# PianoPCB.net
KiCad netlist of a schematic drawn in EAGLE
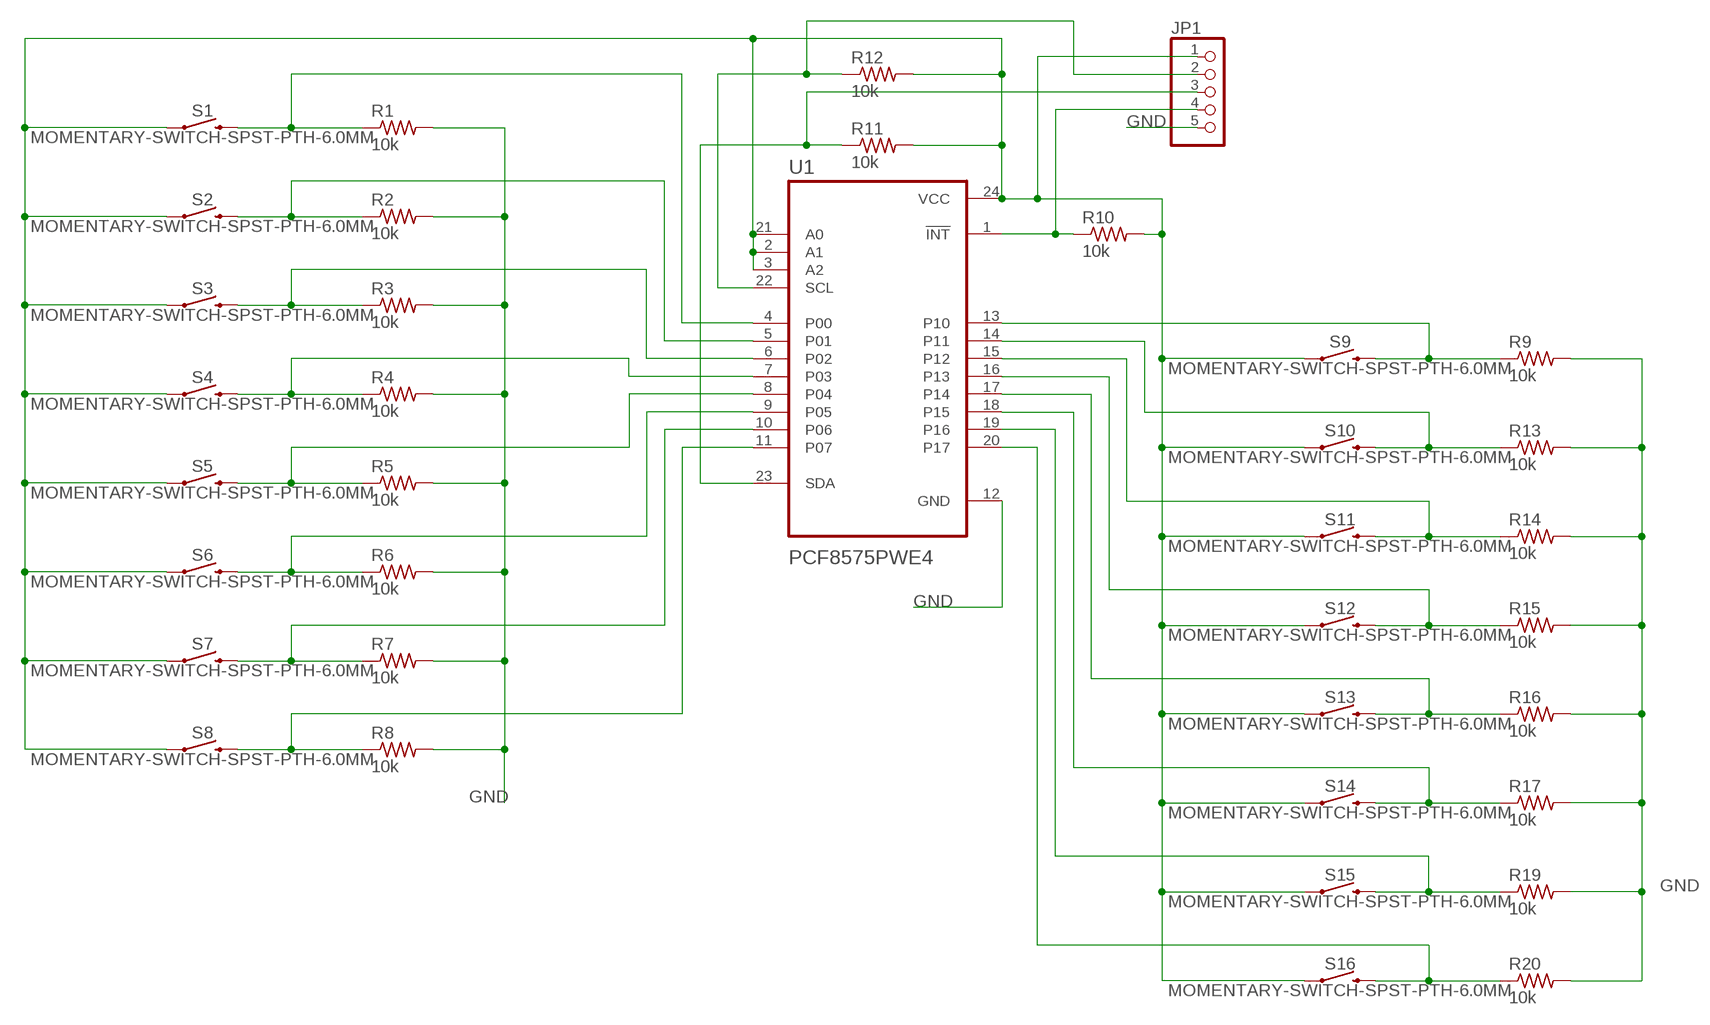
[diagram p0: schematic, sheet 1]

(export (version "E")
  (design (tool "Eeschema 10.0.6"))
  (components
    (comp (ref "JP1")
      (value "PINHD-1X5")
      (footprint "eagle-import:1X05")
      (libsource (lib "eagle-import") (part "PINHD-1X5"))
    )
    (comp (ref "R1")
      (value "10k")
      (footprint "eagle-import:0207_10")
      (libsource (lib "eagle-import") (part "R-US_0207/10"))
    )
    (comp (ref "R2")
      (value "10k")
      (footprint "eagle-import:0207_10")
      (libsource (lib "eagle-import") (part "R-US_0207/10"))
    )
    (comp (ref "R3")
      (value "10k")
      (footprint "eagle-import:0207_10")
      (libsource (lib "eagle-import") (part "R-US_0207/10"))
    )
    (comp (ref "R4")
      (value "10k")
      (footprint "eagle-import:0207_10")
      (libsource (lib "eagle-import") (part "R-US_0207/10"))
    )
    (comp (ref "R5")
      (value "10k")
      (footprint "eagle-import:0207_10")
      (libsource (lib "eagle-import") (part "R-US_0207/10"))
    )
    (comp (ref "R6")
      (value "10k")
      (footprint "eagle-import:0207_10")
      (libsource (lib "eagle-import") (part "R-US_0207/10"))
    )
    (comp (ref "R7")
      (value "10k")
      (footprint "eagle-import:0207_10")
      (libsource (lib "eagle-import") (part "R-US_0207/10"))
    )
    (comp (ref "R8")
      (value "10k")
      (footprint "eagle-import:0207_10")
      (libsource (lib "eagle-import") (part "R-US_0207/10"))
    )
    (comp (ref "R9")
      (value "10k")
      (footprint "eagle-import:0207_10")
      (libsource (lib "eagle-import") (part "R-US_0207/10"))
    )
    (comp (ref "R10")
      (value "10k")
      (footprint "eagle-import:0207_10")
      (libsource (lib "eagle-import") (part "R-US_0207/10"))
    )
    (comp (ref "R11")
      (value "10k")
      (footprint "eagle-import:0207_10")
      (libsource (lib "eagle-import") (part "R-US_0207/10"))
    )
    (comp (ref "R12")
      (value "10k")
      (footprint "eagle-import:0207_10")
      (libsource (lib "eagle-import") (part "R-US_0207/10"))
    )
    (comp (ref "R13")
      (value "10k")
      (footprint "eagle-import:0207_10")
      (libsource (lib "eagle-import") (part "R-US_0207/10"))
    )
    (comp (ref "R14")
      (value "10k")
      (footprint "eagle-import:0207_10")
      (libsource (lib "eagle-import") (part "R-US_0207/10"))
    )
    (comp (ref "R15")
      (value "10k")
      (footprint "eagle-import:0207_10")
      (libsource (lib "eagle-import") (part "R-US_0207/10"))
    )
    (comp (ref "R16")
      (value "10k")
      (footprint "eagle-import:0207_10")
      (libsource (lib "eagle-import") (part "R-US_0207/10"))
    )
    (comp (ref "R17")
      (value "10k")
      (footprint "eagle-import:0207_10")
      (libsource (lib "eagle-import") (part "R-US_0207/10"))
    )
    (comp (ref "R19")
      (value "10k")
      (footprint "eagle-import:0207_10")
      (libsource (lib "eagle-import") (part "R-US_0207/10"))
    )
    (comp (ref "R20")
      (value "10k")
      (footprint "eagle-import:0207_10")
      (libsource (lib "eagle-import") (part "R-US_0207/10"))
    )
    (comp (ref "S1")
      (value "MOMENTARY-SWITCH-SPST-PTH-6.0MM")
      (footprint "eagle-import:TACTILE_SWITCH_PTH_6.0MM")
      (libsource (lib "eagle-import") (part "MOMENTARY-SWITCH-SPST-PTH-6.0MM"))
    )
    (comp (ref "S2")
      (value "MOMENTARY-SWITCH-SPST-PTH-6.0MM")
      (footprint "eagle-import:TACTILE_SWITCH_PTH_6.0MM")
      (libsource (lib "eagle-import") (part "MOMENTARY-SWITCH-SPST-PTH-6.0MM"))
    )
    (comp (ref "S3")
      (value "MOMENTARY-SWITCH-SPST-PTH-6.0MM")
      (footprint "eagle-import:TACTILE_SWITCH_PTH_6.0MM")
      (libsource (lib "eagle-import") (part "MOMENTARY-SWITCH-SPST-PTH-6.0MM"))
    )
    (comp (ref "S4")
      (value "MOMENTARY-SWITCH-SPST-PTH-6.0MM")
      (footprint "eagle-import:TACTILE_SWITCH_PTH_6.0MM")
      (libsource (lib "eagle-import") (part "MOMENTARY-SWITCH-SPST-PTH-6.0MM"))
    )
    (comp (ref "S5")
      (value "MOMENTARY-SWITCH-SPST-PTH-6.0MM")
      (footprint "eagle-import:TACTILE_SWITCH_PTH_6.0MM")
      (libsource (lib "eagle-import") (part "MOMENTARY-SWITCH-SPST-PTH-6.0MM"))
    )
    (comp (ref "S6")
      (value "MOMENTARY-SWITCH-SPST-PTH-6.0MM")
      (footprint "eagle-import:TACTILE_SWITCH_PTH_6.0MM")
      (libsource (lib "eagle-import") (part "MOMENTARY-SWITCH-SPST-PTH-6.0MM"))
    )
    (comp (ref "S7")
      (value "MOMENTARY-SWITCH-SPST-PTH-6.0MM")
      (footprint "eagle-import:TACTILE_SWITCH_PTH_6.0MM")
      (libsource (lib "eagle-import") (part "MOMENTARY-SWITCH-SPST-PTH-6.0MM"))
    )
    (comp (ref "S8")
      (value "MOMENTARY-SWITCH-SPST-PTH-6.0MM")
      (footprint "eagle-import:TACTILE_SWITCH_PTH_6.0MM")
      (libsource (lib "eagle-import") (part "MOMENTARY-SWITCH-SPST-PTH-6.0MM"))
    )
    (comp (ref "S9")
      (value "MOMENTARY-SWITCH-SPST-PTH-6.0MM")
      (footprint "eagle-import:TACTILE_SWITCH_PTH_6.0MM")
      (libsource (lib "eagle-import") (part "MOMENTARY-SWITCH-SPST-PTH-6.0MM"))
    )
    (comp (ref "S10")
      (value "MOMENTARY-SWITCH-SPST-PTH-6.0MM")
      (footprint "eagle-import:TACTILE_SWITCH_PTH_6.0MM")
      (libsource (lib "eagle-import") (part "MOMENTARY-SWITCH-SPST-PTH-6.0MM"))
    )
    (comp (ref "S11")
      (value "MOMENTARY-SWITCH-SPST-PTH-6.0MM")
      (footprint "eagle-import:TACTILE_SWITCH_PTH_6.0MM")
      (libsource (lib "eagle-import") (part "MOMENTARY-SWITCH-SPST-PTH-6.0MM"))
    )
    (comp (ref "S12")
      (value "MOMENTARY-SWITCH-SPST-PTH-6.0MM")
      (footprint "eagle-import:TACTILE_SWITCH_PTH_6.0MM")
      (libsource (lib "eagle-import") (part "MOMENTARY-SWITCH-SPST-PTH-6.0MM"))
    )
    (comp (ref "S13")
      (value "MOMENTARY-SWITCH-SPST-PTH-6.0MM")
      (footprint "eagle-import:TACTILE_SWITCH_PTH_6.0MM")
      (libsource (lib "eagle-import") (part "MOMENTARY-SWITCH-SPST-PTH-6.0MM"))
    )
    (comp (ref "S14")
      (value "MOMENTARY-SWITCH-SPST-PTH-6.0MM")
      (footprint "eagle-import:TACTILE_SWITCH_PTH_6.0MM")
      (libsource (lib "eagle-import") (part "MOMENTARY-SWITCH-SPST-PTH-6.0MM"))
    )
    (comp (ref "S15")
      (value "MOMENTARY-SWITCH-SPST-PTH-6.0MM")
      (footprint "eagle-import:TACTILE_SWITCH_PTH_6.0MM")
      (libsource (lib "eagle-import") (part "MOMENTARY-SWITCH-SPST-PTH-6.0MM"))
    )
    (comp (ref "S16")
      (value "MOMENTARY-SWITCH-SPST-PTH-6.0MM")
      (footprint "eagle-import:TACTILE_SWITCH_PTH_6.0MM")
      (libsource (lib "eagle-import") (part "MOMENTARY-SWITCH-SPST-PTH-6.0MM"))
    )
    (comp (ref "U1")
      (value "PCF8575PWE4")
      (footprint "eagle-import:SOP65P640X120-24N")
      (fields (field (name "MF") "Texas Instruments"))
      (libsource (lib "eagle-import") (part "PCF8575PWE4"))
    )
  )
  (nets
    (net (code "1") (name "/GND") (class "Default")
      (node (ref "JP1") (pin "5") (pinfunction "5_5") (pintype "passive"))
      (node (ref "R1") (pin "2") (pinfunction "2_2") (pintype "passive"))
      (node (ref "R13") (pin "2") (pinfunction "2_2") (pintype "passive"))
      (node (ref "R14") (pin "2") (pinfunction "2_2") (pintype "passive"))
      (node (ref "R15") (pin "2") (pinfunction "2_2") (pintype "passive"))
      (node (ref "R16") (pin "2") (pinfunction "2_2") (pintype "passive"))
      (node (ref "R17") (pin "2") (pinfunction "2_2") (pintype "passive"))
      (node (ref "R19") (pin "2") (pinfunction "2_2") (pintype "passive"))
      (node (ref "R2") (pin "2") (pinfunction "2_2") (pintype "passive"))
      (node (ref "R20") (pin "2") (pinfunction "2_2") (pintype "passive"))
      (node (ref "R3") (pin "2") (pinfunction "2_2") (pintype "passive"))
      (node (ref "R4") (pin "2") (pinfunction "2_2") (pintype "passive"))
      (node (ref "R5") (pin "2") (pinfunction "2_2") (pintype "passive"))
      (node (ref "R6") (pin "2") (pinfunction "2_2") (pintype "passive"))
      (node (ref "R7") (pin "2") (pinfunction "2_2") (pintype "passive"))
      (node (ref "R8") (pin "2") (pinfunction "2_2") (pintype "passive"))
      (node (ref "R9") (pin "2") (pinfunction "2_2") (pintype "passive"))
      (node (ref "U1") (pin "12") (pinfunction "GND_12") (pintype "power_in"))
    )
    (net (code "2") (name "Net-(S1-2)") (class "Default")
      (node (ref "R1") (pin "1") (pinfunction "1_1") (pintype "passive"))
      (node (ref "S1") (pin "3") (pinfunction "2_3") (pintype "passive"))
      (node (ref "U1") (pin "4") (pinfunction "P00_4") (pintype "bidirectional"))
    )
    (net (code "3") (name "Net-(S2-2)") (class "Default")
      (node (ref "R2") (pin "1") (pinfunction "1_1") (pintype "passive"))
      (node (ref "S2") (pin "3") (pinfunction "2_3") (pintype "passive"))
      (node (ref "U1") (pin "5") (pinfunction "P01_5") (pintype "bidirectional"))
    )
    (net (code "4") (name "Net-(S3-2)") (class "Default")
      (node (ref "R3") (pin "1") (pinfunction "1_1") (pintype "passive"))
      (node (ref "S3") (pin "3") (pinfunction "2_3") (pintype "passive"))
      (node (ref "U1") (pin "6") (pinfunction "P02_6") (pintype "bidirectional"))
    )
    (net (code "5") (name "Net-(S4-2)") (class "Default")
      (node (ref "R4") (pin "1") (pinfunction "1_1") (pintype "passive"))
      (node (ref "S4") (pin "3") (pinfunction "2_3") (pintype "passive"))
      (node (ref "U1") (pin "7") (pinfunction "P03_7") (pintype "bidirectional"))
    )
    (net (code "6") (name "Net-(S5-2)") (class "Default")
      (node (ref "R5") (pin "1") (pinfunction "1_1") (pintype "passive"))
      (node (ref "S5") (pin "3") (pinfunction "2_3") (pintype "passive"))
      (node (ref "U1") (pin "8") (pinfunction "P04_8") (pintype "bidirectional"))
    )
    (net (code "7") (name "Net-(S6-2)") (class "Default")
      (node (ref "R6") (pin "1") (pinfunction "1_1") (pintype "passive"))
      (node (ref "S6") (pin "3") (pinfunction "2_3") (pintype "passive"))
      (node (ref "U1") (pin "9") (pinfunction "P05_9") (pintype "bidirectional"))
    )
    (net (code "8") (name "Net-(S7-2)") (class "Default")
      (node (ref "R7") (pin "1") (pinfunction "1_1") (pintype "passive"))
      (node (ref "S7") (pin "3") (pinfunction "2_3") (pintype "passive"))
      (node (ref "U1") (pin "10") (pinfunction "P06_10") (pintype "bidirectional"))
    )
    (net (code "9") (name "Net-(S8-2)") (class "Default")
      (node (ref "R8") (pin "1") (pinfunction "1_1") (pintype "passive"))
      (node (ref "S8") (pin "3") (pinfunction "2_3") (pintype "passive"))
      (node (ref "U1") (pin "11") (pinfunction "P07_11") (pintype "bidirectional"))
    )
    (net (code "10") (name "Net-(S9-2)") (class "Default")
      (node (ref "R9") (pin "1") (pinfunction "1_1") (pintype "passive"))
      (node (ref "S9") (pin "3") (pinfunction "2_3") (pintype "passive"))
      (node (ref "U1") (pin "13") (pinfunction "P10_13") (pintype "bidirectional"))
    )
    (net (code "11") (name "Net-(S10-2)") (class "Default")
      (node (ref "R13") (pin "1") (pinfunction "1_1") (pintype "passive"))
      (node (ref "S10") (pin "3") (pinfunction "2_3") (pintype "passive"))
      (node (ref "U1") (pin "14") (pinfunction "P11_14") (pintype "bidirectional"))
    )
    (net (code "12") (name "Net-(S11-2)") (class "Default")
      (node (ref "R14") (pin "1") (pinfunction "1_1") (pintype "passive"))
      (node (ref "S11") (pin "3") (pinfunction "2_3") (pintype "passive"))
      (node (ref "U1") (pin "15") (pinfunction "P12_15") (pintype "bidirectional"))
    )
    (net (code "13") (name "Net-(S12-2)") (class "Default")
      (node (ref "R15") (pin "1") (pinfunction "1_1") (pintype "passive"))
      (node (ref "S12") (pin "3") (pinfunction "2_3") (pintype "passive"))
      (node (ref "U1") (pin "16") (pinfunction "P13_16") (pintype "bidirectional"))
    )
    (net (code "14") (name "Net-(S13-2)") (class "Default")
      (node (ref "R16") (pin "1") (pinfunction "1_1") (pintype "passive"))
      (node (ref "S13") (pin "3") (pinfunction "2_3") (pintype "passive"))
      (node (ref "U1") (pin "17") (pinfunction "P14_17") (pintype "bidirectional"))
    )
    (net (code "15") (name "Net-(S14-2)") (class "Default")
      (node (ref "R17") (pin "1") (pinfunction "1_1") (pintype "passive"))
      (node (ref "S14") (pin "3") (pinfunction "2_3") (pintype "passive"))
      (node (ref "U1") (pin "18") (pinfunction "P15_18") (pintype "bidirectional"))
    )
    (net (code "16") (name "Net-(S15-2)") (class "Default")
      (node (ref "R19") (pin "1") (pinfunction "1_1") (pintype "passive"))
      (node (ref "S15") (pin "3") (pinfunction "2_3") (pintype "passive"))
      (node (ref "U1") (pin "19") (pinfunction "P16_19") (pintype "bidirectional"))
    )
    (net (code "17") (name "Net-(S16-2)") (class "Default")
      (node (ref "R20") (pin "1") (pinfunction "1_1") (pintype "passive"))
      (node (ref "S16") (pin "3") (pinfunction "2_3") (pintype "passive"))
      (node (ref "U1") (pin "20") (pinfunction "P17_20") (pintype "bidirectional"))
    )
    (net (code "18") (name "Net-(U1-A0)") (class "Default")
      (node (ref "JP1") (pin "1") (pinfunction "1_1") (pintype "passive"))
      (node (ref "R10") (pin "2") (pinfunction "2_2") (pintype "passive"))
      (node (ref "R11") (pin "2") (pinfunction "2_2") (pintype "passive"))
      (node (ref "R12") (pin "2") (pinfunction "2_2") (pintype "passive"))
      (node (ref "S1") (pin "1") (pinfunction "1_1") (pintype "passive"))
      (node (ref "S10") (pin "1") (pinfunction "1_1") (pintype "passive"))
      (node (ref "S11") (pin "1") (pinfunction "1_1") (pintype "passive"))
      (node (ref "S12") (pin "1") (pinfunction "1_1") (pintype "passive"))
      (node (ref "S13") (pin "1") (pinfunction "1_1") (pintype "passive"))
      (node (ref "S14") (pin "1") (pinfunction "1_1") (pintype "passive"))
      (node (ref "S15") (pin "1") (pinfunction "1_1") (pintype "passive"))
      (node (ref "S16") (pin "1") (pinfunction "1_1") (pintype "passive"))
      (node (ref "S2") (pin "1") (pinfunction "1_1") (pintype "passive"))
      (node (ref "S3") (pin "1") (pinfunction "1_1") (pintype "passive"))
      (node (ref "S4") (pin "1") (pinfunction "1_1") (pintype "passive"))
      (node (ref "S5") (pin "1") (pinfunction "1_1") (pintype "passive"))
      (node (ref "S6") (pin "1") (pinfunction "1_1") (pintype "passive"))
      (node (ref "S7") (pin "1") (pinfunction "1_1") (pintype "passive"))
      (node (ref "S8") (pin "1") (pinfunction "1_1") (pintype "passive"))
      (node (ref "S9") (pin "1") (pinfunction "1_1") (pintype "passive"))
      (node (ref "U1") (pin "2") (pinfunction "A1_2") (pintype "input"))
      (node (ref "U1") (pin "21") (pinfunction "A0_21") (pintype "input"))
      (node (ref "U1") (pin "24") (pinfunction "VCC_24") (pintype "power_in"))
      (node (ref "U1") (pin "3") (pinfunction "A2_3") (pintype "input"))
    )
    (net (code "19") (name "Net-(U1-SCL)") (class "Default")
      (node (ref "JP1") (pin "2") (pinfunction "2_2") (pintype "passive"))
      (node (ref "R12") (pin "1") (pinfunction "1_1") (pintype "passive"))
      (node (ref "U1") (pin "22") (pinfunction "SCL_22") (pintype "input"))
    )
    (net (code "20") (name "Net-(U1-SDA)") (class "Default")
      (node (ref "JP1") (pin "3") (pinfunction "3_3") (pintype "passive"))
      (node (ref "R11") (pin "1") (pinfunction "1_1") (pintype "passive"))
      (node (ref "U1") (pin "23") (pinfunction "SDA_23") (pintype "bidirectional"))
    )
    (net (code "21") (name "Net-(U1-~{INT})") (class "Default")
      (node (ref "JP1") (pin "4") (pinfunction "4_4") (pintype "passive"))
      (node (ref "R10") (pin "1") (pinfunction "1_1") (pintype "passive"))
      (node (ref "U1") (pin "1") (pinfunction "~{INT}_1") (pintype "output"))
    )
  )
)
